# MotorControl.net
KiCad netlist of a schematic drawn in Altium Designer
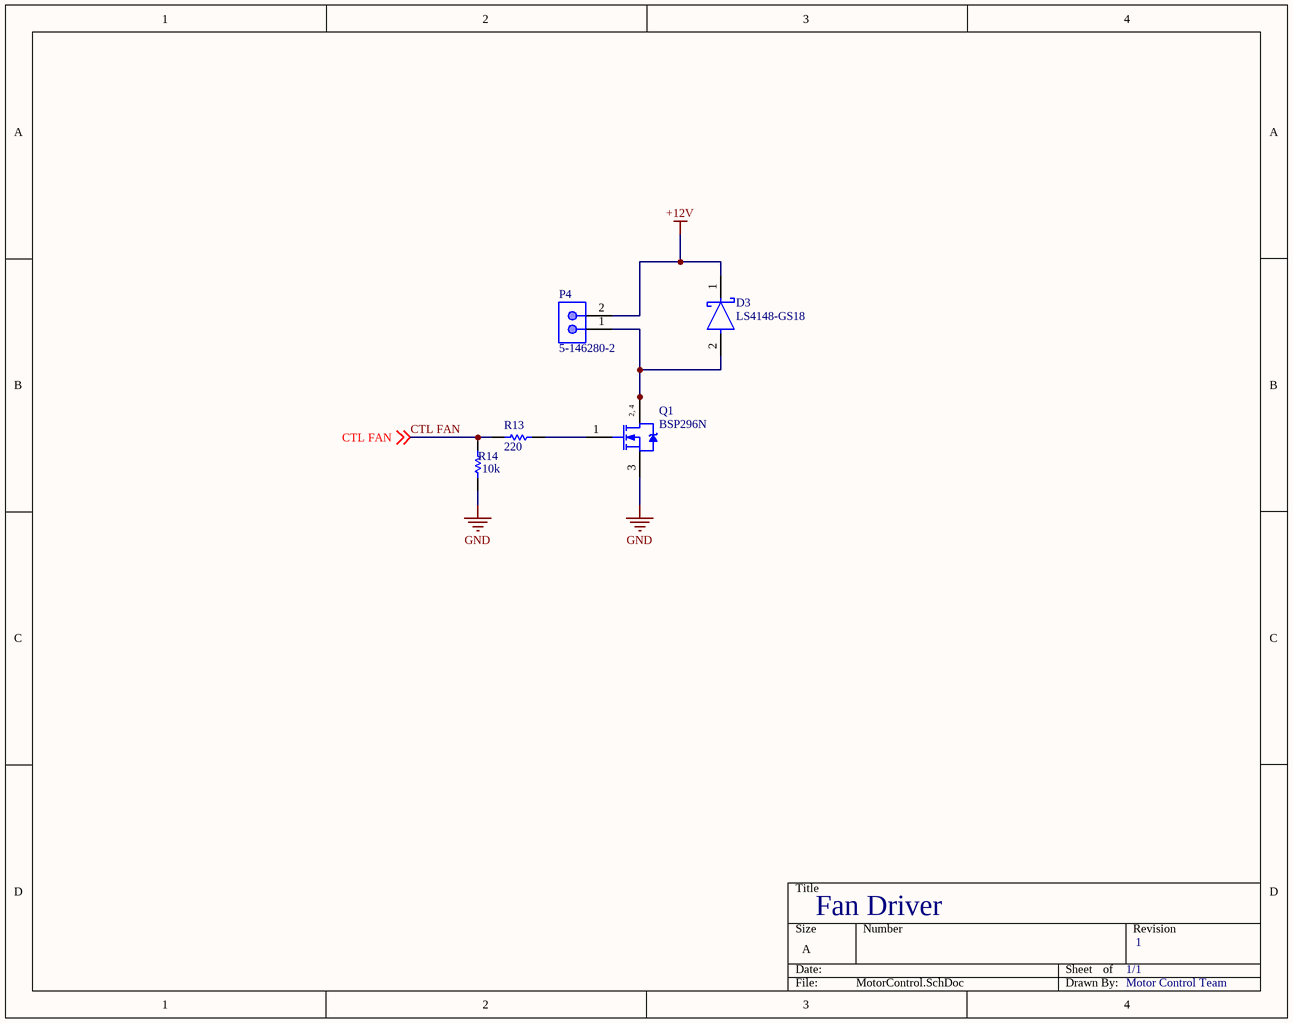
[diagram p0: MotorControl.SchDoc]

(export (version "E")
  (design (tool "Eeschema 10.0.6"))
  (components
    (comp (ref "D3")
      (value "LS4148-GS18")
      (footprint "FP-6_560-5006_01-4-MFG")
      (description "DIODE GEN PURP 75V 150MA SOD80\r\n LCSC Part # C145227")
      (fields
        (field (name "MANUFACTURER") "Vishay")
        (field (name "OCTOPART") "https://octopart.com/ls4148-gs18-vishay-55507867")
      )
      (libsource (lib "Altium Content Vault") (part "1d6ec82d83fb6aee721767c19dac4b9"))
    )
    (comp (ref "P4")
      (value "5-146280-2")
      (footprint "TECO-5-146280-2_V")
      (fields (field (name "MANUFACTURER") "TE Connectivity"))
      (libsource (lib "Altium Content Vault") (part "CN-1P-M-R2"))
    )
    (comp (ref "Q1")
      (value "BSP296N")
      (footprint "INF-PG-SOT223_SC-73_M")
      (fields (field (name "MANUFACTURER") "Infineon") (field (name "PARTNUMBER") "BSP89"))
      (libsource (lib "Altium Content Vault") (part "INF-NEMOS-GDSD-4-B"))
    )
    (comp (ref "R13")
      (value "220")
      (footprint "RESC2013X70X40ML20T20")
      (description "Chip Resistor, 1 KOhm, +/- 1%, 0.125 W, -55 to 155 degC, 0805 (2013 Metric)")
      (fields (field (name "POWER") "125mW") (field (name "TOLERANCE") "1%"))
      (libsource (lib "Formula Racing at UC Davis") (part "RES-2"))
    )
    (comp (ref "R14")
      (value "10k")
      (footprint "RESC2013X70X40ML20T20")
      (description "Chip Resistor, 1 KOhm, +/- 1%, 0.125 W, -55 to 155 degC, 0805 (2013 Metric)")
      (fields (field (name "POWER") "125mW") (field (name "TOLERANCE") "1%"))
      (libsource (lib "Formula Racing at UC Davis") (part "RES-2"))
    )
  )
  (nets
    (net (code "1") (name "+12V") (class "Default")
      (node (ref "D3") (pin "1") (pinfunction "C_1") (pintype "passive"))
      (node (ref "P4") (pin "2") (pinfunction "2_2") (pintype "passive"))
    )
    (net (code "2") (name "CTL FAN") (class "Default")
      (node (ref "R13") (pin "2") (pinfunction "2_2") (pintype "passive"))
      (node (ref "R14") (pin "2") (pinfunction "2_2") (pintype "passive"))
    )
    (net (code "3") (name "GND") (class "Default")
      (node (ref "Q1") (pin "3") (pinfunction "SOURCE_3") (pintype "passive"))
      (node (ref "R14") (pin "1") (pinfunction "1_1") (pintype "passive"))
    )
    (net (code "4") (name "Net-(D3-A)") (class "Default")
      (node (ref "D3") (pin "2") (pinfunction "A_2") (pintype "passive"))
      (node (ref "P4") (pin "1") (pinfunction "1_1") (pintype "passive"))
      (node (ref "Q1") (pin "2") (pinfunction "DRAIN_2") (pintype "passive"))
      (node (ref "Q1") (pin "4") (pinfunction "DRAIN_4") (pintype "passive"))
    )
    (net (code "5") (name "Net-(Q1-GATE)") (class "Default")
      (node (ref "Q1") (pin "1") (pinfunction "GATE_1") (pintype "passive"))
      (node (ref "R13") (pin "1") (pinfunction "1_1") (pintype "passive"))
    )
  )
)
